# spi_lcd_onesided.net
KiCad netlist of a schematic drawn in EAGLE
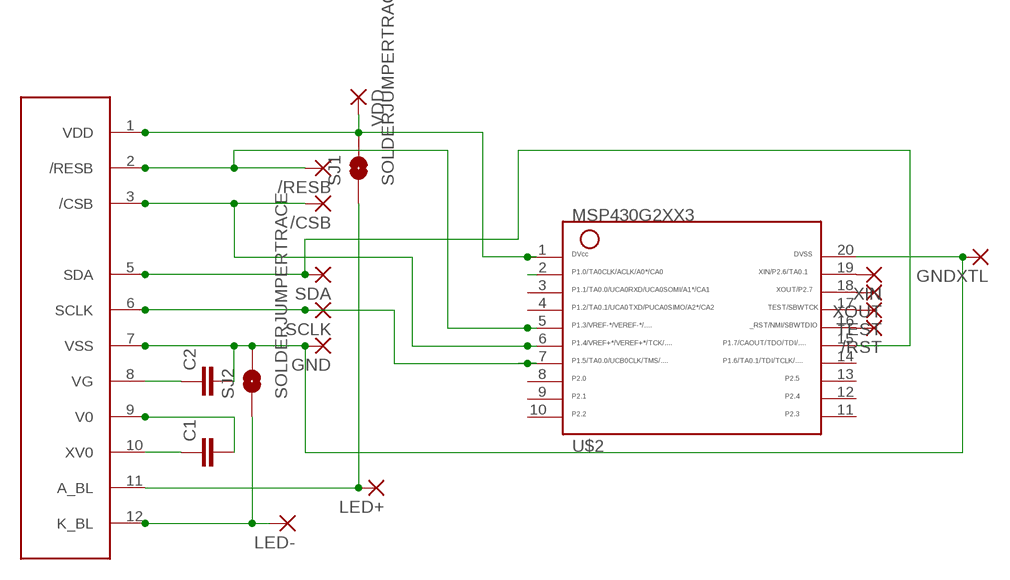
[diagram p0: schematic, sheet 1]

(export (version "E")
  (design (tool "Eeschema 10.0.6"))
  (components
    (comp (ref "/CSB")
      (value "1,6/0,9")
      (footprint "eagle-import:1,6_0,9")
      (libsource (lib "eagle-import") (part "1,6/0,9"))
    )
    (comp (ref "/RESB")
      (value "1,6/0,9")
      (footprint "eagle-import:1,6_0,9")
      (libsource (lib "eagle-import") (part "1,6/0,9"))
    )
    (comp (ref "/RST")
      (value "1,6/0,9")
      (footprint "eagle-import:1,6_0,9")
      (libsource (lib "eagle-import") (part "1,6/0,9"))
    )
    (comp (ref "C1")
      (value "CAP0805")
      (footprint "eagle-import:0805")
      (libsource (lib "eagle-import") (part "CAP0805"))
    )
    (comp (ref "C2")
      (value "CAP0805")
      (footprint "eagle-import:0805")
      (libsource (lib "eagle-import") (part "CAP0805"))
    )
    (comp (ref "GND")
      (value "1,6/0,9")
      (footprint "eagle-import:1,6_0,9")
      (libsource (lib "eagle-import") (part "1,6/0,9"))
    )
    (comp (ref "GNDXTL")
      (value "SMD2")
      (footprint "eagle-import:SMD1,27-2,54")
      (libsource (lib "eagle-import") (part "SMD2"))
    )
    (comp (ref "LED+")
      (value "1,6/0,9")
      (footprint "eagle-import:1,6_0,9")
      (libsource (lib "eagle-import") (part "1,6/0,9"))
    )
    (comp (ref "LED-")
      (value "1,6/0,9")
      (footprint "eagle-import:1,6_0,9")
      (libsource (lib "eagle-import") (part "1,6/0,9"))
    )
    (comp (ref "SCLK")
      (value "1,6/0,9")
      (footprint "eagle-import:1,6_0,9")
      (libsource (lib "eagle-import") (part "1,6/0,9"))
    )
    (comp (ref "SDA")
      (value "1,6/0,9")
      (footprint "eagle-import:1,6_0,9")
      (libsource (lib "eagle-import") (part "1,6/0,9"))
    )
    (comp (ref "SJ1")
      (value "SOLDERJUMPERTRACE")
      (footprint "eagle-import:SJ_2S-TRACE")
      (libsource (lib "eagle-import") (part "SOLDERJUMPERTRACE"))
    )
    (comp (ref "SJ2")
      (value "SOLDERJUMPERTRACE")
      (footprint "eagle-import:SJ_2S-TRACE")
      (libsource (lib "eagle-import") (part "SOLDERJUMPERTRACE"))
    )
    (comp (ref "TEST")
      (value "1,6/0,9")
      (footprint "eagle-import:1,6_0,9")
      (libsource (lib "eagle-import") (part "1,6/0,9"))
    )
    (comp (ref "U$1")
      (value "PE9665WRFPE9665WRF-WHOLE")
      (footprint "eagle-import:PE9665WRF")
      (libsource (lib "eagle-import") (part "PE9665WRFPE9665WRF-WHOLE"))
    )
    (comp (ref "U$2")
      (value "G2XX3---PW20")
      (footprint "eagle-import:PW20")
      (libsource (lib "eagle-import") (part "G2XX3---PW20"))
    )
    (comp (ref "VDD")
      (value "1,6/0,9")
      (footprint "eagle-import:1,6_0,9")
      (libsource (lib "eagle-import") (part "1,6/0,9"))
    )
    (comp (ref "XIN")
      (value "SMD2")
      (footprint "eagle-import:SMD1,27-2,54")
      (libsource (lib "eagle-import") (part "SMD2"))
    )
    (comp (ref "XOUT")
      (value "SMD2")
      (footprint "eagle-import:SMD1,27-2,54")
      (libsource (lib "eagle-import") (part "SMD2"))
    )
  )
  (nets
    (net (code "1") (name "Net-(/CSB-P)") (class "Default")
      (node (ref "/CSB") (pin "1") (pinfunction "P_1") (pintype "passive"))
      (node (ref "U$1") (pin "3") (pinfunction "/CSB_3") (pintype "bidirectional"))
      (node (ref "U$2") (pin "6") (pinfunction "6_6") (pintype "bidirectional"))
    )
    (net (code "2") (name "Net-(/RESB-P)") (class "Default")
      (node (ref "/RESB") (pin "1") (pinfunction "P_1") (pintype "passive"))
      (node (ref "U$1") (pin "2") (pinfunction "/RESB_2") (pintype "bidirectional"))
      (node (ref "U$2") (pin "5") (pinfunction "5_5") (pintype "bidirectional"))
    )
    (net (code "3") (name "Net-(/RST-P)") (class "Default")
      (node (ref "/RST") (pin "1") (pinfunction "P_1") (pintype "passive"))
      (node (ref "U$2") (pin "16") (pinfunction "16_16") (pintype "bidirectional"))
    )
    (net (code "4") (name "Net-(GND-P)") (class "Default")
      (node (ref "C2") (pin "2") (pinfunction "2_2") (pintype "passive"))
      (node (ref "GND") (pin "1") (pinfunction "P_1") (pintype "passive"))
      (node (ref "GNDXTL") (pin "1") (pinfunction "P_1") (pintype "passive"))
      (node (ref "SJ2") (pin "2") (pinfunction "2_2") (pintype "passive"))
      (node (ref "U$1") (pin "7") (pinfunction "VSS_7") (pintype "bidirectional"))
      (node (ref "U$2") (pin "20") (pinfunction "20_20") (pintype "bidirectional"))
    )
    (net (code "5") (name "Net-(LED+-P)") (class "Default")
      (node (ref "LED+") (pin "1") (pinfunction "P_1") (pintype "passive"))
      (node (ref "SJ1") (pin "1") (pinfunction "1_1") (pintype "passive"))
      (node (ref "U$1") (pin "11") (pinfunction "A_BL_11") (pintype "bidirectional"))
    )
    (net (code "6") (name "Net-(LED--P)") (class "Default")
      (node (ref "LED-") (pin "1") (pinfunction "P_1") (pintype "passive"))
      (node (ref "SJ2") (pin "1") (pinfunction "1_1") (pintype "passive"))
      (node (ref "U$1") (pin "12") (pinfunction "K_BL_12") (pintype "bidirectional"))
    )
    (net (code "7") (name "Net-(SCLK-P)") (class "Default")
      (node (ref "SCLK") (pin "1") (pinfunction "P_1") (pintype "passive"))
      (node (ref "U$1") (pin "6") (pinfunction "SCLK_6") (pintype "bidirectional"))
      (node (ref "U$2") (pin "7") (pinfunction "7_7") (pintype "bidirectional"))
    )
    (net (code "8") (name "Net-(SDA-P)") (class "Default")
      (node (ref "SDA") (pin "1") (pinfunction "P_1") (pintype "passive"))
      (node (ref "U$1") (pin "5") (pinfunction "SDA_5") (pintype "bidirectional"))
      (node (ref "U$2") (pin "15") (pinfunction "15_15") (pintype "bidirectional"))
    )
    (net (code "9") (name "Net-(TEST-P)") (class "Default")
      (node (ref "TEST") (pin "1") (pinfunction "P_1") (pintype "passive"))
      (node (ref "U$2") (pin "17") (pinfunction "17_17") (pintype "bidirectional"))
    )
    (net (code "10") (name "Net-(U$1-V0)") (class "Default")
      (node (ref "C1") (pin "2") (pinfunction "2_2") (pintype "passive"))
      (node (ref "U$1") (pin "9") (pinfunction "V0_9") (pintype "bidirectional"))
    )
    (net (code "11") (name "Net-(U$1-VDD)") (class "Default")
      (node (ref "SJ1") (pin "2") (pinfunction "2_2") (pintype "passive"))
      (node (ref "U$1") (pin "1") (pinfunction "VDD_1") (pintype "bidirectional"))
      (node (ref "U$2") (pin "1") (pinfunction "1_1") (pintype "bidirectional"))
      (node (ref "VDD") (pin "1") (pinfunction "P_1") (pintype "passive"))
    )
    (net (code "12") (name "Net-(U$1-VG)") (class "Default")
      (node (ref "C2") (pin "1") (pinfunction "1_1") (pintype "passive"))
      (node (ref "U$1") (pin "8") (pinfunction "VG_8") (pintype "bidirectional"))
    )
    (net (code "13") (name "Net-(U$1-XV0)") (class "Default")
      (node (ref "C1") (pin "1") (pinfunction "1_1") (pintype "passive"))
      (node (ref "U$1") (pin "10") (pinfunction "XV0_10") (pintype "bidirectional"))
    )
    (net (code "14") (name "Net-(XIN-P)") (class "Default")
      (node (ref "U$2") (pin "19") (pinfunction "19_19") (pintype "bidirectional"))
      (node (ref "XIN") (pin "1") (pinfunction "P_1") (pintype "passive"))
    )
    (net (code "15") (name "Net-(XOUT-P)") (class "Default")
      (node (ref "U$2") (pin "18") (pinfunction "18_18") (pintype "bidirectional"))
      (node (ref "XOUT") (pin "1") (pinfunction "P_1") (pintype "passive"))
    )
    (net (code "16") (name "unconnected-(U$2-Pad2)") (class "Default")
      (node (ref "U$2") (pin "2") (pinfunction "2_2") (pintype "bidirectional"))
    )
    (net (code "17") (name "unconnected-(U$2-Pad3)") (class "Default")
      (node (ref "U$2") (pin "3") (pinfunction "3_3") (pintype "bidirectional"))
    )
    (net (code "18") (name "unconnected-(U$2-Pad4)") (class "Default")
      (node (ref "U$2") (pin "4") (pinfunction "4_4") (pintype "bidirectional"))
    )
    (net (code "19") (name "unconnected-(U$2-Pad8)") (class "Default")
      (node (ref "U$2") (pin "8") (pinfunction "8_8") (pintype "bidirectional"))
    )
    (net (code "20") (name "unconnected-(U$2-Pad9)") (class "Default")
      (node (ref "U$2") (pin "9") (pinfunction "9_9") (pintype "bidirectional"))
    )
    (net (code "21") (name "unconnected-(U$2-Pad10)") (class "Default")
      (node (ref "U$2") (pin "10") (pinfunction "10_10") (pintype "bidirectional"))
    )
    (net (code "22") (name "unconnected-(U$2-Pad11)") (class "Default")
      (node (ref "U$2") (pin "11") (pinfunction "11_11") (pintype "bidirectional"))
    )
    (net (code "23") (name "unconnected-(U$2-Pad12)") (class "Default")
      (node (ref "U$2") (pin "12") (pinfunction "12_12") (pintype "bidirectional"))
    )
    (net (code "24") (name "unconnected-(U$2-Pad13)") (class "Default")
      (node (ref "U$2") (pin "13") (pinfunction "13_13") (pintype "bidirectional"))
    )
    (net (code "25") (name "unconnected-(U$2-Pad14)") (class "Default")
      (node (ref "U$2") (pin "14") (pinfunction "14_14") (pintype "bidirectional"))
    )
  )
)
